# Protect.net
KiCad netlist of a schematic drawn in Altium Designer
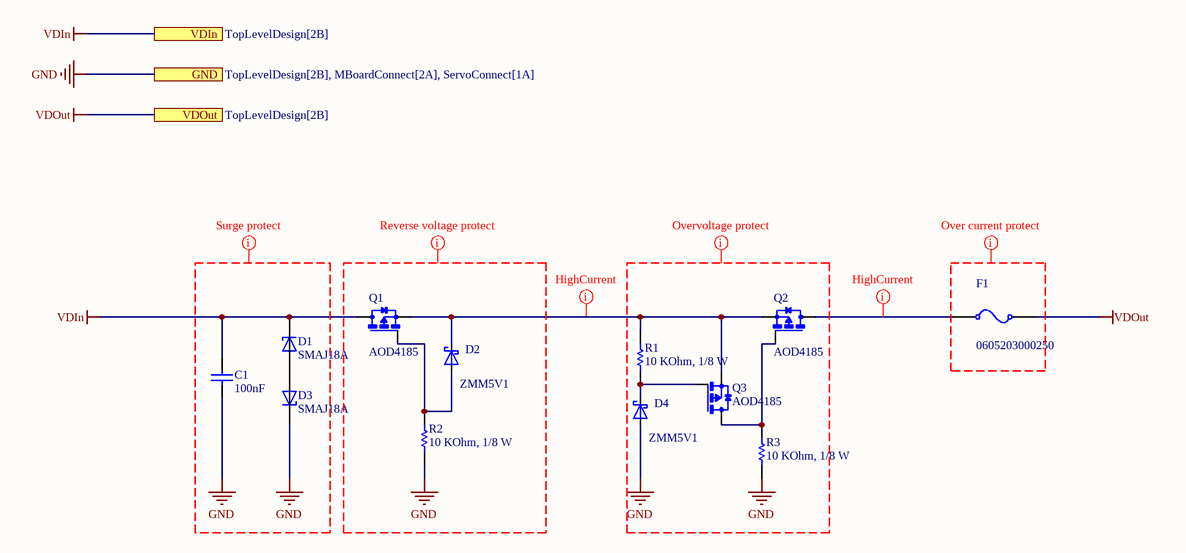
[diagram p0: Protect.SchDoc]

(export (version "E")
  (design (tool "Eeschema 10.0.6"))
  (components
    (comp (ref "C1")
      (value "100nF")
      (footprint "CAP_0805")
      (description "CAP, size 0805, 0.1 nF, 50 VDC")
      (fields
        (field (name "TOLERANCE") "10%")
        (field (name "Comment") "0108051041050")
        (field (name "SOURCE") "Capacitor_0805_10_percent.SchLib")
      )
      (libsource (lib "Tin Tran") (part "0108056841050"))
    )
    (comp (ref "D1")
      (value "SMAJ18A")
      (footprint "DIOM4325X250N")
      (description "400W, 21.1V, 5%, Unidirectional, TVS")
      (fields (field (name "MF") "Taiwan Semiconductor"))
      (libsource (lib "Tin Tran") (part "SMAJ18A"))
    )
    (comp (ref "D2")
      (value "ZMM5V1")
      (footprint "SOD-80_MiniMELF_Glass")
      (libsource (lib "Tin Tran") (part "Schottky-Diode"))
    )
    (comp (ref "D3")
      (value "SMAJ18A")
      (footprint "DIOM4325X250N")
      (description "400W, 21.1V, 5%, Unidirectional, TVS")
      (fields (field (name "MF") "Taiwan Semiconductor"))
      (libsource (lib "Tin Tran") (part "SMAJ18A"))
    )
    (comp (ref "D4")
      (value "ZMM5V1")
      (footprint "SOD-80_MiniMELF_Glass")
      (libsource (lib "Tin Tran") (part "Schottky-Diode"))
    )
    (comp (ref "F1")
      (value "0605203000250")
      (footprint "Fuse_Clip_0520")
      (description "Ceramic Fuse, Size 0520, 250 VAC, 30A")
      (fields (field (name "MANUFACTURER") "Littelfuse"))
      (libsource (lib "Tin Tran") (part "0605201000250F"))
    )
    (comp (ref "Q1")
      (value "AOD4185")
      (footprint "DPAK")
      (description "P-Channel 40V 40A (Tc) 2.5W (Ta), 62.5W (Tc) Surface Mount TO-252, (D-Pak)")
      (fields (field (name "MF") "Alpha &"))
      (libsource (lib "Tin Tran") (part "AOD4185"))
    )
    (comp (ref "Q2")
      (value "AOD4185")
      (footprint "DPAK")
      (description "P-Channel 40V 40A (Tc) 2.5W (Ta), 62.5W (Tc) Surface Mount TO-252, (D-Pak)")
      (fields (field (name "MF") "Alpha &"))
      (libsource (lib "") (part "AOD4185_1"))
    )
    (comp (ref "Q3")
      (value "AOD4185")
      (footprint "DPAK")
      (description "P-Channel 40V 40A (Tc) 2.5W (Ta), 62.5W (Tc) Surface Mount TO-252, (D-Pak)")
      (fields (field (name "MF") "Alpha &"))
      (libsource (lib "Tin Tran") (part "AOD4185"))
    )
    (comp (ref "R1")
      (value "10 KOhm, 1/8 W")
      (footprint "RESISTOR_0805")
      (description "RES, size 0805, 10 KOhm, 1/8 W")
      (fields (field (name "Comment") "0008051031"))
      (libsource (lib "Tin Tran") (part "0008052035_1"))
    )
    (comp (ref "R2")
      (value "10 KOhm, 1/8 W")
      (footprint "RESISTOR_0805")
      (description "RES, size 0805, 10 KOhm, 1/8 W")
      (fields (field (name "Comment") "0008051031"))
      (libsource (lib "Tin Tran") (part "0008052035_1"))
    )
    (comp (ref "R3")
      (value "10 KOhm, 1/8 W")
      (footprint "RESISTOR_0805")
      (description "RES, size 0805, 10 KOhm, 1/8 W")
      (fields (field (name "Comment") "0008051031"))
      (libsource (lib "Tin Tran") (part "0008052035_1"))
    )
  )
  (nets
    (net (code "1") (name "GND") (class "Default")
      (node (ref "C1") (pin "1") (pinfunction "1_1") (pintype "passive"))
      (node (ref "D3") (pin "C") (pinfunction "C_C") (pintype "passive"))
      (node (ref "D4") (pin "A") (pinfunction "A_A") (pintype "passive"))
      (node (ref "R2") (pin "1") (pinfunction "1_1") (pintype "passive"))
      (node (ref "R3") (pin "1") (pinfunction "1_1") (pintype "passive"))
    )
    (net (code "2") (name "Net-(D1-PadA)") (class "Default")
      (node (ref "D1") (pin "A") (pinfunction "A_A") (pintype "passive"))
      (node (ref "D3") (pin "A") (pinfunction "A_A") (pintype "passive"))
    )
    (net (code "3") (name "Net-(Q1-G)") (class "Default")
      (node (ref "D2") (pin "A") (pinfunction "A_A") (pintype "passive"))
      (node (ref "Q1") (pin "1") (pinfunction "G_1") (pintype "passive"))
      (node (ref "R2") (pin "2") (pinfunction "2_2") (pintype "passive"))
    )
    (net (code "4") (name "Net-(Q1-S)") (class "Default")
      (node (ref "D2") (pin "K") (pinfunction "K_K") (pintype "passive"))
      (node (ref "Q1") (pin "3") (pinfunction "S_3") (pintype "passive"))
      (node (ref "Q2") (pin "3") (pinfunction "S_3") (pintype "passive"))
      (node (ref "Q3") (pin "3") (pinfunction "S_3") (pintype "passive"))
      (node (ref "R1") (pin "2") (pinfunction "2_2") (pintype "passive"))
    )
    (net (code "5") (name "Net-(Q2-D)") (class "Default")
      (node (ref "F1") (pin "0") (pinfunction "0_0") (pintype "passive"))
      (node (ref "Q2") (pin "4") (pinfunction "D_4") (pintype "passive"))
    )
    (net (code "6") (name "Net-(Q2-G)") (class "Default")
      (node (ref "Q2") (pin "1") (pinfunction "G_1") (pintype "passive"))
      (node (ref "Q3") (pin "4") (pinfunction "D_4") (pintype "passive"))
      (node (ref "R3") (pin "2") (pinfunction "2_2") (pintype "passive"))
    )
    (net (code "7") (name "Net-(Q3-G)") (class "Default")
      (node (ref "D4") (pin "K") (pinfunction "K_K") (pintype "passive"))
      (node (ref "Q3") (pin "1") (pinfunction "G_1") (pintype "passive"))
      (node (ref "R1") (pin "1") (pinfunction "1_1") (pintype "passive"))
    )
    (net (code "8") (name "VDIn") (class "Default")
      (node (ref "C1") (pin "2") (pinfunction "2_2") (pintype "passive"))
      (node (ref "D1") (pin "C") (pinfunction "C_C") (pintype "passive"))
      (node (ref "Q1") (pin "4") (pinfunction "D_4") (pintype "passive"))
    )
    (net (code "9") (name "VDOut") (class "Default")
      (node (ref "F1") (pin "1") (pinfunction "1_1") (pintype "passive"))
    )
  )
)
